# 5_UnitConnector.net
KiCad netlist of a schematic drawn in Altium Designer
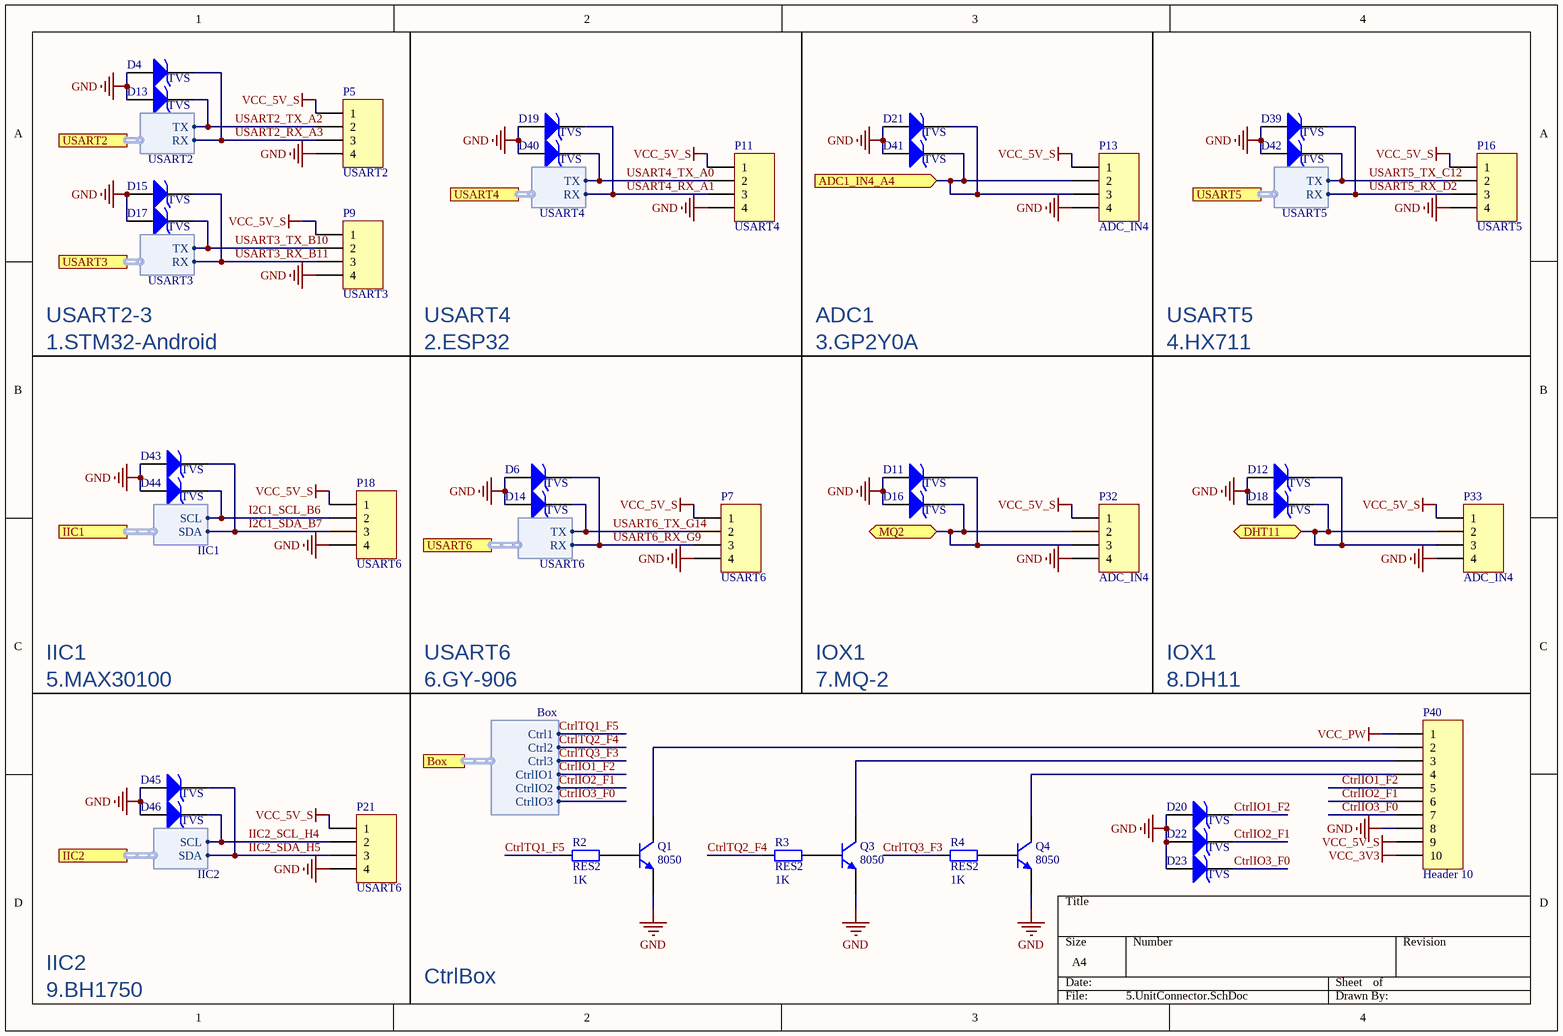
[diagram p0: 5.UnitConnector.SchDoc]

(export (version "E")
  (design (tool "Eeschema 10.0.6"))
  (components
    (comp (ref "D4")
      (value "TVS")
      (footprint "SOD-523")
      (description "High Conductance Fast Diode")
      (fields (field (name "PUBLISHER") "Altium Limited"))
      (libsource (lib "QT") (part "D"))
    )
    (comp (ref "D6")
      (value "TVS")
      (footprint "SOD-523")
      (description "High Conductance Fast Diode")
      (fields (field (name "PUBLISHER") "Altium Limited"))
      (libsource (lib "QT") (part "D"))
    )
    (comp (ref "D11")
      (value "TVS")
      (footprint "SOD-523")
      (description "High Conductance Fast Diode")
      (fields (field (name "PUBLISHER") "Altium Limited"))
      (libsource (lib "QT") (part "D"))
    )
    (comp (ref "D12")
      (value "TVS")
      (footprint "SOD-523")
      (description "High Conductance Fast Diode")
      (fields (field (name "PUBLISHER") "Altium Limited"))
      (libsource (lib "QT") (part "D"))
    )
    (comp (ref "D13")
      (value "TVS")
      (footprint "SOD-523")
      (description "High Conductance Fast Diode")
      (fields (field (name "PUBLISHER") "Altium Limited"))
      (libsource (lib "QT") (part "D"))
    )
    (comp (ref "D14")
      (value "TVS")
      (footprint "SOD-523")
      (description "High Conductance Fast Diode")
      (fields (field (name "PUBLISHER") "Altium Limited"))
      (libsource (lib "QT") (part "D"))
    )
    (comp (ref "D15")
      (value "TVS")
      (footprint "SOD-523")
      (description "High Conductance Fast Diode")
      (fields (field (name "PUBLISHER") "Altium Limited"))
      (libsource (lib "QT") (part "D"))
    )
    (comp (ref "D16")
      (value "TVS")
      (footprint "SOD-523")
      (description "High Conductance Fast Diode")
      (fields (field (name "PUBLISHER") "Altium Limited"))
      (libsource (lib "QT") (part "D"))
    )
    (comp (ref "D17")
      (value "TVS")
      (footprint "SOD-523")
      (description "High Conductance Fast Diode")
      (fields (field (name "PUBLISHER") "Altium Limited"))
      (libsource (lib "QT") (part "D"))
    )
    (comp (ref "D18")
      (value "TVS")
      (footprint "SOD-523")
      (description "High Conductance Fast Diode")
      (fields (field (name "PUBLISHER") "Altium Limited"))
      (libsource (lib "QT") (part "D"))
    )
    (comp (ref "D19")
      (value "TVS")
      (footprint "SOD-523")
      (description "High Conductance Fast Diode")
      (fields (field (name "PUBLISHER") "Altium Limited"))
      (libsource (lib "QT") (part "D"))
    )
    (comp (ref "D20")
      (value "TVS")
      (footprint "SOD-523")
      (description "High Conductance Fast Diode")
      (fields (field (name "PUBLISHER") "Altium Limited"))
      (libsource (lib "QT") (part "D"))
    )
    (comp (ref "D21")
      (value "TVS")
      (footprint "SOD-523")
      (description "High Conductance Fast Diode")
      (fields (field (name "PUBLISHER") "Altium Limited"))
      (libsource (lib "QT") (part "D"))
    )
    (comp (ref "D22")
      (value "TVS")
      (footprint "SOD-523")
      (description "High Conductance Fast Diode")
      (fields (field (name "PUBLISHER") "Altium Limited"))
      (libsource (lib "QT") (part "D"))
    )
    (comp (ref "D23")
      (value "TVS")
      (footprint "SOD-523")
      (description "High Conductance Fast Diode")
      (fields (field (name "PUBLISHER") "Altium Limited"))
      (libsource (lib "QT") (part "D"))
    )
    (comp (ref "D39")
      (value "TVS")
      (footprint "SOD-523")
      (description "High Conductance Fast Diode")
      (fields (field (name "PUBLISHER") "Altium Limited"))
      (libsource (lib "QT") (part "D"))
    )
    (comp (ref "D40")
      (value "TVS")
      (footprint "SOD-523")
      (description "High Conductance Fast Diode")
      (fields (field (name "PUBLISHER") "Altium Limited"))
      (libsource (lib "QT") (part "D"))
    )
    (comp (ref "D41")
      (value "TVS")
      (footprint "SOD-523")
      (description "High Conductance Fast Diode")
      (fields (field (name "PUBLISHER") "Altium Limited"))
      (libsource (lib "QT") (part "D"))
    )
    (comp (ref "D42")
      (value "TVS")
      (footprint "SOD-523")
      (description "High Conductance Fast Diode")
      (fields (field (name "PUBLISHER") "Altium Limited"))
      (libsource (lib "QT") (part "D"))
    )
    (comp (ref "D43")
      (value "TVS")
      (footprint "SOD-523")
      (description "High Conductance Fast Diode")
      (fields (field (name "PUBLISHER") "Altium Limited"))
      (libsource (lib "QT") (part "D"))
    )
    (comp (ref "D44")
      (value "TVS")
      (footprint "SOD-523")
      (description "High Conductance Fast Diode")
      (fields (field (name "PUBLISHER") "Altium Limited"))
      (libsource (lib "QT") (part "D"))
    )
    (comp (ref "D45")
      (value "TVS")
      (footprint "SOD-523")
      (description "High Conductance Fast Diode")
      (fields (field (name "PUBLISHER") "Altium Limited"))
      (libsource (lib "QT") (part "D"))
    )
    (comp (ref "D46")
      (value "TVS")
      (footprint "SOD-523")
      (description "High Conductance Fast Diode")
      (fields (field (name "PUBLISHER") "Altium Limited"))
      (libsource (lib "QT") (part "D"))
    )
    (comp (ref "P5")
      (value "USART2")
      (footprint "KF2EDGK-2.54-WI-4P")
      (description "Header, 4-Pin")
      (fields (field (name "PUBLISHER") "Altium Limited"))
      (libsource (lib "QT") (part "Header 4"))
    )
    (comp (ref "P7")
      (value "USART6")
      (footprint "KF2EDGK-2.54-WI-4P")
      (description "Header, 4-Pin")
      (fields (field (name "PUBLISHER") "Altium Limited"))
      (libsource (lib "QT") (part "Header 4"))
    )
    (comp (ref "P9")
      (value "USART3")
      (footprint "KF2EDGK-2.54-WI-4P")
      (description "Header, 4-Pin")
      (fields (field (name "PUBLISHER") "Altium Limited"))
      (libsource (lib "QT") (part "Header 4"))
    )
    (comp (ref "P11")
      (value "USART4")
      (footprint "KF2EDGK-2.54-WI-4P")
      (description "Header, 4-Pin")
      (fields (field (name "PUBLISHER") "Altium Limited"))
      (libsource (lib "QT") (part "Header 4"))
    )
    (comp (ref "P13")
      (value "ADC_IN4")
      (footprint "KF2EDGK-2.54-WI-4P")
      (description "Header, 4-Pin")
      (fields (field (name "PUBLISHER") "Altium Limited"))
      (libsource (lib "QT") (part "Header 4"))
    )
    (comp (ref "P16")
      (value "USART5")
      (footprint "KF2EDGK-2.54-WI-4P")
      (description "Header, 4-Pin")
      (fields (field (name "PUBLISHER") "Altium Limited"))
      (libsource (lib "QT") (part "Header 4"))
    )
    (comp (ref "P18")
      (value "USART6")
      (footprint "KF2EDGK-2.54-WI-4P")
      (description "Header, 4-Pin")
      (fields (field (name "PUBLISHER") "Altium Limited"))
      (libsource (lib "QT") (part "Header 4"))
    )
    (comp (ref "P21")
      (value "USART6")
      (footprint "KF2EDGK-2.54-WI-4P")
      (description "Header, 4-Pin")
      (fields (field (name "PUBLISHER") "Altium Limited"))
      (libsource (lib "QT") (part "Header 4"))
    )
    (comp (ref "P32")
      (value "ADC_IN4")
      (footprint "KF2EDGK-2.54-WI-4P")
      (description "Header, 4-Pin")
      (fields (field (name "PUBLISHER") "Altium Limited"))
      (libsource (lib "QT") (part "Header 4"))
    )
    (comp (ref "P33")
      (value "ADC_IN4")
      (footprint "KF2EDGK-2.54-WI-4P")
      (description "Header, 4-Pin")
      (fields (field (name "PUBLISHER") "Altium Limited"))
      (libsource (lib "QT") (part "Header 4"))
    )
    (comp (ref "P40")
      (value "Header 10")
      (footprint "KF2EDGK-2.54-WI-10P")
      (description "Header, 10-Pin")
      (fields (field (name "PUBLISHER") "Altium Limited"))
      (libsource (lib "Miscellaneous Connectors") (part "Header 10"))
    )
    (comp (ref "Q1")
      (value "8050")
      (footprint "SOT23-3L")
      (description "NPN Bipolar Transistor")
      (fields (field (name "PUBLISHER") "Altium Limited"))
      (libsource (lib "QT") (part "NPN  SOT"))
    )
    (comp (ref "Q3")
      (value "8050")
      (footprint "SOT23-3L")
      (description "NPN Bipolar Transistor")
      (fields (field (name "PUBLISHER") "Altium Limited"))
      (libsource (lib "QT") (part "NPN  SOT"))
    )
    (comp (ref "Q4")
      (value "8050")
      (footprint "SOT23-3L")
      (description "NPN Bipolar Transistor")
      (fields (field (name "PUBLISHER") "Altium Limited"))
      (libsource (lib "QT") (part "NPN  SOT"))
    )
    (comp (ref "R2")
      (value "RES2")
      (footprint "R 0805_L")
      (description "Resistor")
      (fields (field (name "ALTIUM_VALUE") "1K") (field (name "PUBLISHER") "Altium Limited"))
      (libsource (lib "QT") (part "RES2"))
    )
    (comp (ref "R3")
      (value "RES2")
      (footprint "R 0805_L")
      (description "Resistor")
      (fields (field (name "ALTIUM_VALUE") "1K") (field (name "PUBLISHER") "Altium Limited"))
      (libsource (lib "QT") (part "RES2"))
    )
    (comp (ref "R4")
      (value "RES2")
      (footprint "R 0805_L")
      (description "Resistor")
      (fields (field (name "ALTIUM_VALUE") "1K") (field (name "PUBLISHER") "Altium Limited"))
      (libsource (lib "QT") (part "RES2"))
    )
  )
  (nets
    (net (code "9") (name "/ADC1_IN4_A4") (class "Default")
      (node (ref "D21") (pin "2") (pinfunction "K_2") (pintype "passive"))
      (node (ref "D41") (pin "2") (pinfunction "K_2") (pintype "passive"))
      (node (ref "P13") (pin "2") (pinfunction "2_2") (pintype "passive"))
      (node (ref "P13") (pin "3") (pinfunction "3_3") (pintype "passive"))
    )
    (net (code "10") (name "/CtrlIO1_F2") (class "Default")
      (node (ref "D20") (pin "2") (pinfunction "K_2") (pintype "passive"))
      (node (ref "P40") (pin "5") (pinfunction "5_5") (pintype "passive"))
    )
    (net (code "11") (name "/CtrlIO2_F1") (class "Default")
      (node (ref "D22") (pin "2") (pinfunction "K_2") (pintype "passive"))
      (node (ref "P40") (pin "6") (pinfunction "6_6") (pintype "passive"))
    )
    (net (code "12") (name "/CtrlIO3_F0") (class "Default")
      (node (ref "D23") (pin "2") (pinfunction "K_2") (pintype "passive"))
      (node (ref "P40") (pin "7") (pinfunction "7_7") (pintype "passive"))
    )
    (net (code "13") (name "/CtrlTQ1_F5") (class "Default")
      (node (ref "R2") (pin "2") (pinfunction "2_2") (pintype "passive"))
    )
    (net (code "14") (name "/CtrlTQ2_F4") (class "Default")
      (node (ref "R3") (pin "2") (pinfunction "2_2") (pintype "passive"))
    )
    (net (code "15") (name "/CtrlTQ3_F3") (class "Default")
      (node (ref "R4") (pin "2") (pinfunction "2_2") (pintype "passive"))
    )
    (net (code "16") (name "/DHT11") (class "Default")
      (node (ref "D12") (pin "2") (pinfunction "K_2") (pintype "passive"))
      (node (ref "D18") (pin "2") (pinfunction "K_2") (pintype "passive"))
      (node (ref "P33") (pin "2") (pinfunction "2_2") (pintype "passive"))
      (node (ref "P33") (pin "3") (pinfunction "3_3") (pintype "passive"))
    )
    (net (code "17") (name "/I2C1_SCL_B6") (class "Default")
      (node (ref "D44") (pin "2") (pinfunction "K_2") (pintype "passive"))
      (node (ref "P18") (pin "2") (pinfunction "2_2") (pintype "passive"))
    )
    (net (code "18") (name "/I2C1_SDA_B7") (class "Default")
      (node (ref "D43") (pin "2") (pinfunction "K_2") (pintype "passive"))
      (node (ref "P18") (pin "3") (pinfunction "3_3") (pintype "passive"))
    )
    (net (code "19") (name "/IIC2_SCL_H4") (class "Default")
      (node (ref "D46") (pin "2") (pinfunction "K_2") (pintype "passive"))
      (node (ref "P21") (pin "2") (pinfunction "2_2") (pintype "passive"))
    )
    (net (code "20") (name "/IIC2_SDA_H5") (class "Default")
      (node (ref "D45") (pin "2") (pinfunction "K_2") (pintype "passive"))
      (node (ref "P21") (pin "3") (pinfunction "3_3") (pintype "passive"))
    )
    (net (code "21") (name "/MQ2") (class "Default")
      (node (ref "D11") (pin "2") (pinfunction "K_2") (pintype "passive"))
      (node (ref "D16") (pin "2") (pinfunction "K_2") (pintype "passive"))
      (node (ref "P32") (pin "2") (pinfunction "2_2") (pintype "passive"))
      (node (ref "P32") (pin "3") (pinfunction "3_3") (pintype "passive"))
    )
    (net (code "22") (name "/USART2_RX_A3") (class "Default")
      (node (ref "D4") (pin "2") (pinfunction "K_2") (pintype "passive"))
      (node (ref "P5") (pin "3") (pinfunction "3_3") (pintype "passive"))
    )
    (net (code "23") (name "/USART2_TX_A2") (class "Default")
      (node (ref "D13") (pin "2") (pinfunction "K_2") (pintype "passive"))
      (node (ref "P5") (pin "2") (pinfunction "2_2") (pintype "passive"))
    )
    (net (code "24") (name "/USART3_RX_B11") (class "Default")
      (node (ref "D15") (pin "2") (pinfunction "K_2") (pintype "passive"))
      (node (ref "P9") (pin "3") (pinfunction "3_3") (pintype "passive"))
    )
    (net (code "25") (name "/USART3_TX_B10") (class "Default")
      (node (ref "D17") (pin "2") (pinfunction "K_2") (pintype "passive"))
      (node (ref "P9") (pin "2") (pinfunction "2_2") (pintype "passive"))
    )
    (net (code "26") (name "/USART4_RX_A1") (class "Default")
      (node (ref "D19") (pin "2") (pinfunction "K_2") (pintype "passive"))
      (node (ref "P11") (pin "3") (pinfunction "3_3") (pintype "passive"))
    )
    (net (code "27") (name "/USART4_TX_A0") (class "Default")
      (node (ref "D40") (pin "2") (pinfunction "K_2") (pintype "passive"))
      (node (ref "P11") (pin "2") (pinfunction "2_2") (pintype "passive"))
    )
    (net (code "28") (name "/USART5_RX_D2") (class "Default")
      (node (ref "D39") (pin "2") (pinfunction "K_2") (pintype "passive"))
      (node (ref "P16") (pin "3") (pinfunction "3_3") (pintype "passive"))
    )
    (net (code "29") (name "/USART5_TX_C12") (class "Default")
      (node (ref "D42") (pin "2") (pinfunction "K_2") (pintype "passive"))
      (node (ref "P16") (pin "2") (pinfunction "2_2") (pintype "passive"))
    )
    (net (code "30") (name "/USART6_RX_G9") (class "Default")
      (node (ref "D6") (pin "2") (pinfunction "K_2") (pintype "passive"))
      (node (ref "P7") (pin "3") (pinfunction "3_3") (pintype "passive"))
    )
    (net (code "31") (name "/USART6_TX_G14") (class "Default")
      (node (ref "D14") (pin "2") (pinfunction "K_2") (pintype "passive"))
      (node (ref "P7") (pin "2") (pinfunction "2_2") (pintype "passive"))
    )
    (net (code "40") (name "GND") (class "Default")
      (node (ref "D11") (pin "1") (pinfunction "A_1") (pintype "passive"))
      (node (ref "D12") (pin "1") (pinfunction "A_1") (pintype "passive"))
      (node (ref "D13") (pin "1") (pinfunction "A_1") (pintype "passive"))
      (node (ref "D14") (pin "1") (pinfunction "A_1") (pintype "passive"))
      (node (ref "D15") (pin "1") (pinfunction "A_1") (pintype "passive"))
      (node (ref "D16") (pin "1") (pinfunction "A_1") (pintype "passive"))
      (node (ref "D17") (pin "1") (pinfunction "A_1") (pintype "passive"))
      (node (ref "D18") (pin "1") (pinfunction "A_1") (pintype "passive"))
      (node (ref "D19") (pin "1") (pinfunction "A_1") (pintype "passive"))
      (node (ref "D20") (pin "1") (pinfunction "A_1") (pintype "passive"))
      (node (ref "D21") (pin "1") (pinfunction "A_1") (pintype "passive"))
      (node (ref "D22") (pin "1") (pinfunction "A_1") (pintype "passive"))
      (node (ref "D23") (pin "1") (pinfunction "A_1") (pintype "passive"))
      (node (ref "D39") (pin "1") (pinfunction "A_1") (pintype "passive"))
      (node (ref "D4") (pin "1") (pinfunction "A_1") (pintype "passive"))
      (node (ref "D40") (pin "1") (pinfunction "A_1") (pintype "passive"))
      (node (ref "D41") (pin "1") (pinfunction "A_1") (pintype "passive"))
      (node (ref "D42") (pin "1") (pinfunction "A_1") (pintype "passive"))
      (node (ref "D43") (pin "1") (pinfunction "A_1") (pintype "passive"))
      (node (ref "D44") (pin "1") (pinfunction "A_1") (pintype "passive"))
      (node (ref "D45") (pin "1") (pinfunction "A_1") (pintype "passive"))
      (node (ref "D46") (pin "1") (pinfunction "A_1") (pintype "passive"))
      (node (ref "D6") (pin "1") (pinfunction "A_1") (pintype "passive"))
      (node (ref "P11") (pin "4") (pinfunction "4_4") (pintype "passive"))
      (node (ref "P13") (pin "4") (pinfunction "4_4") (pintype "passive"))
      (node (ref "P16") (pin "4") (pinfunction "4_4") (pintype "passive"))
      (node (ref "P18") (pin "4") (pinfunction "4_4") (pintype "passive"))
      (node (ref "P21") (pin "4") (pinfunction "4_4") (pintype "passive"))
      (node (ref "P32") (pin "4") (pinfunction "4_4") (pintype "passive"))
      (node (ref "P33") (pin "4") (pinfunction "4_4") (pintype "passive"))
      (node (ref "P40") (pin "8") (pinfunction "8_8") (pintype "passive"))
      (node (ref "P5") (pin "4") (pinfunction "4_4") (pintype "passive"))
      (node (ref "P7") (pin "4") (pinfunction "4_4") (pintype "passive"))
      (node (ref "P9") (pin "4") (pinfunction "4_4") (pintype "passive"))
      (node (ref "Q1") (pin "2") (pinfunction "E_2") (pintype "passive"))
      (node (ref "Q3") (pin "2") (pinfunction "E_2") (pintype "passive"))
      (node (ref "Q4") (pin "2") (pinfunction "E_2") (pintype "passive"))
    )
    (net (code "41") (name "Net-(Q1-B)") (class "Default")
      (node (ref "Q1") (pin "1") (pinfunction "B_1") (pintype "passive"))
      (node (ref "R2") (pin "1") (pinfunction "1_1") (pintype "passive"))
    )
    (net (code "42") (name "Net-(Q1-C)") (class "Default")
      (node (ref "P40") (pin "2") (pinfunction "2_2") (pintype "passive"))
      (node (ref "Q1") (pin "3") (pinfunction "C_3") (pintype "passive"))
    )
    (net (code "43") (name "Net-(Q3-B)") (class "Default")
      (node (ref "Q3") (pin "1") (pinfunction "B_1") (pintype "passive"))
      (node (ref "R3") (pin "1") (pinfunction "1_1") (pintype "passive"))
    )
    (net (code "44") (name "Net-(Q3-C)") (class "Default")
      (node (ref "P40") (pin "3") (pinfunction "3_3") (pintype "passive"))
      (node (ref "Q3") (pin "3") (pinfunction "C_3") (pintype "passive"))
    )
    (net (code "45") (name "Net-(Q4-B)") (class "Default")
      (node (ref "Q4") (pin "1") (pinfunction "B_1") (pintype "passive"))
      (node (ref "R4") (pin "1") (pinfunction "1_1") (pintype "passive"))
    )
    (net (code "46") (name "Net-(Q4-C)") (class "Default")
      (node (ref "P40") (pin "4") (pinfunction "4_4") (pintype "passive"))
      (node (ref "Q4") (pin "3") (pinfunction "C_3") (pintype "passive"))
    )
    (net (code "47") (name "VCC_3V3") (class "Default")
      (node (ref "P40") (pin "10") (pinfunction "10_10") (pintype "passive"))
    )
    (net (code "48") (name "VCC_5V_S") (class "Default")
      (node (ref "P11") (pin "1") (pinfunction "1_1") (pintype "passive"))
      (node (ref "P13") (pin "1") (pinfunction "1_1") (pintype "passive"))
      (node (ref "P16") (pin "1") (pinfunction "1_1") (pintype "passive"))
      (node (ref "P18") (pin "1") (pinfunction "1_1") (pintype "passive"))
      (node (ref "P21") (pin "1") (pinfunction "1_1") (pintype "passive"))
      (node (ref "P32") (pin "1") (pinfunction "1_1") (pintype "passive"))
      (node (ref "P33") (pin "1") (pinfunction "1_1") (pintype "passive"))
      (node (ref "P40") (pin "9") (pinfunction "9_9") (pintype "passive"))
      (node (ref "P5") (pin "1") (pinfunction "1_1") (pintype "passive"))
      (node (ref "P7") (pin "1") (pinfunction "1_1") (pintype "passive"))
      (node (ref "P9") (pin "1") (pinfunction "1_1") (pintype "passive"))
    )
    (net (code "49") (name "VCC_PW") (class "Default")
      (node (ref "P40") (pin "1") (pinfunction "1_1") (pintype "passive"))
    )
  )
)
